# isoCAN.net
KiCad netlist of a schematic drawn in Altium Designer
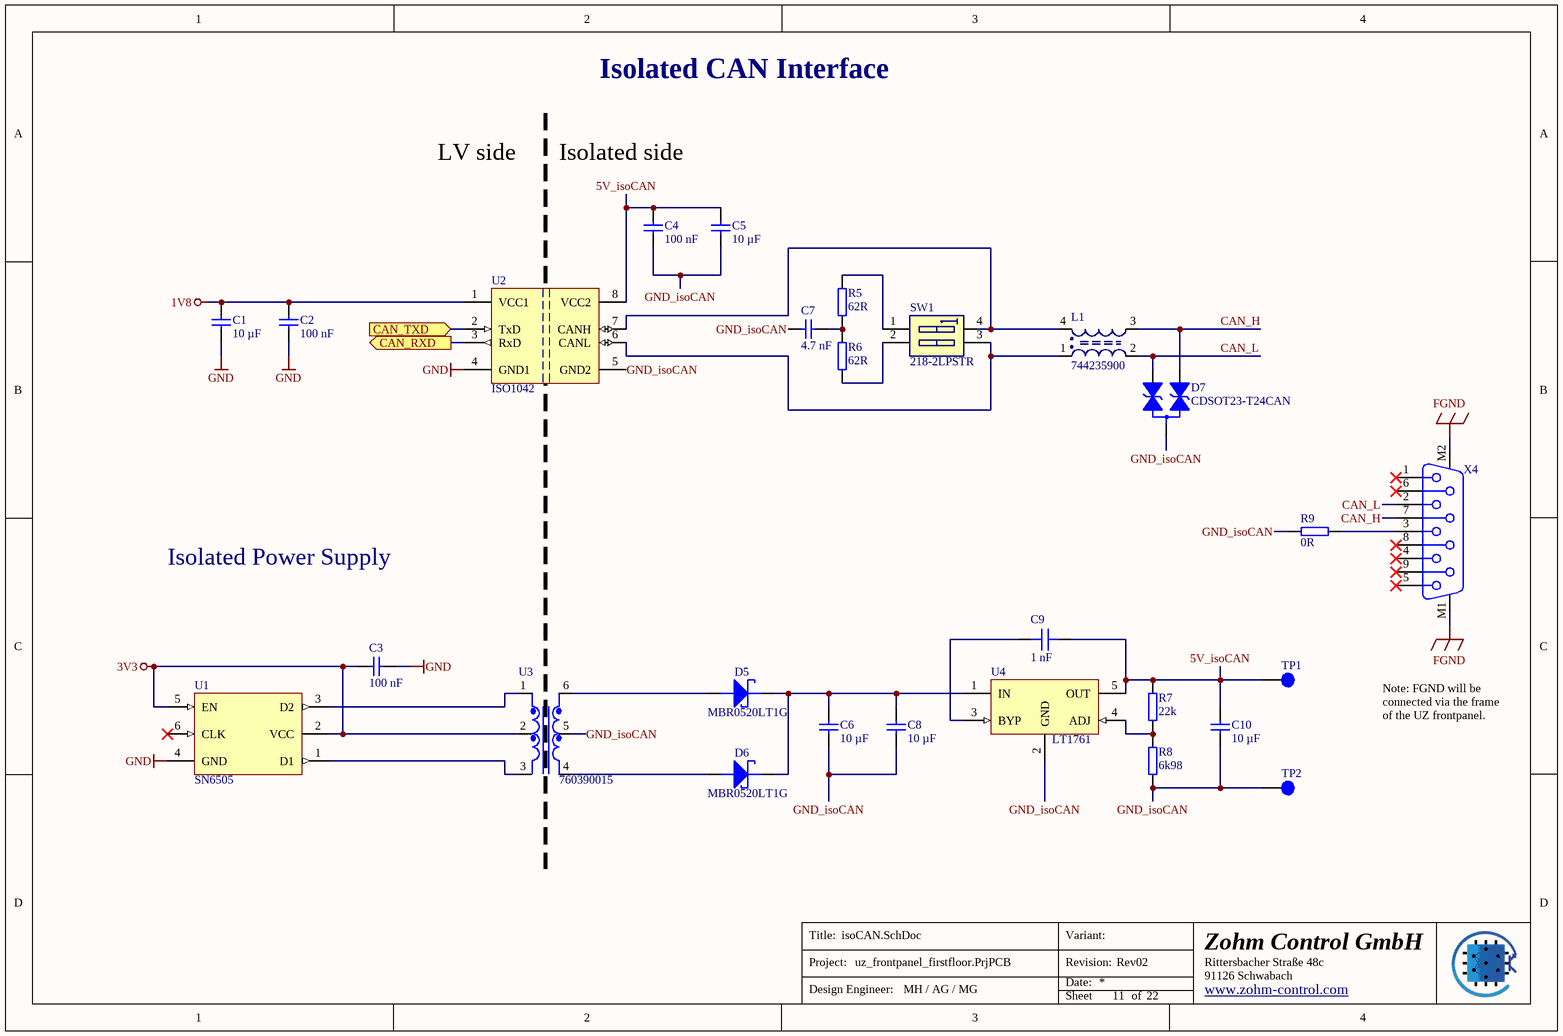
[diagram p0: isoCAN.SchDoc]

(export (version "E")
  (design (tool "Eeschema 10.0.6"))
  (components
    (comp (ref "C1")
      (value "10 µF")
      (footprint "C_0603_TE")
      (description "Generic capacitor")
      (fields
        (field (name "MANUFACTURER PART NUMBER") "UZgen_C_0603_10uF_16V_X7R")
        (field (name "MANUFACTURER") "UZgen")
        (field (name "CREATED FROM") "UZgenTool")
      )
      (libsource (lib "user") (part "CAP-NP"))
    )
    (comp (ref "C2")
      (value "100 nF")
      (footprint "C_0603_TE")
      (description "Generic capacitor")
      (fields
        (field (name "MANUFACTURER PART NUMBER") "UZgen_C_0603_100nF_50V_X7R")
        (field (name "MANUFACTURER") "UZgen")
        (field (name "CREATED FROM") "AGeiger")
      )
      (libsource (lib "user") (part "CAP-NP"))
    )
    (comp (ref "C3")
      (value "100 nF")
      (footprint "C_0603_TE")
      (description "Generic capacitor")
      (fields
        (field (name "MANUFACTURER PART NUMBER") "UZgen_C_0603_100nF_50V_X7R")
        (field (name "MANUFACTURER") "UZgen")
        (field (name "CREATED FROM") "AGeiger")
      )
      (libsource (lib "user") (part "CAP-NP"))
    )
    (comp (ref "C4")
      (value "100 nF")
      (footprint "C_0603_TE")
      (description "Generic capacitor")
      (fields
        (field (name "MANUFACTURER PART NUMBER") "UZgen_C_0603_100nF_50V_X7R")
        (field (name "MANUFACTURER") "UZgen")
        (field (name "CREATED FROM") "AGeiger")
      )
      (libsource (lib "user") (part "CAP-NP"))
    )
    (comp (ref "C5")
      (value "10 µF")
      (footprint "C_0603_TE")
      (description "Generic capacitor")
      (fields
        (field (name "MANUFACTURER PART NUMBER") "UZgen_C_0603_10uF_16V_X7R")
        (field (name "MANUFACTURER") "UZgen")
        (field (name "CREATED FROM") "UZgenTool")
      )
      (libsource (lib "user") (part "CAP-NP"))
    )
    (comp (ref "C6")
      (value "10 µF")
      (footprint "C_0603_TE")
      (description "Generic capacitor")
      (fields
        (field (name "MANUFACTURER PART NUMBER") "UZgen_C_0603_10uF_16V_X7R")
        (field (name "MANUFACTURER") "UZgen")
        (field (name "CREATED FROM") "UZgenTool")
      )
      (libsource (lib "user") (part "CAP-NP"))
    )
    (comp (ref "C7")
      (value "4.7 nF")
      (footprint "C_0603_TE")
      (description "Generic capacitor")
      (fields
        (field (name "MANUFACTURER PART NUMBER") "UZgen_C_0603_4.7nF_50V_X7R")
        (field (name "MANUFACTURER") "UZgen")
        (field (name "CREATED FROM") "UZgenTool")
      )
      (libsource (lib "user") (part "CAP-NP"))
    )
    (comp (ref "C8")
      (value "10 µF")
      (footprint "C_0603_TE")
      (description "Generic capacitor")
      (fields
        (field (name "MANUFACTURER PART NUMBER") "UZgen_C_0603_10uF_16V_X7R")
        (field (name "MANUFACTURER") "UZgen")
        (field (name "CREATED FROM") "UZgenTool")
      )
      (libsource (lib "user") (part "CAP-NP"))
    )
    (comp (ref "C9")
      (value "1 nF")
      (footprint "C_0603")
      (description "Capacitor 0603, 50 VDC, 1 nF, NP0")
      (fields
        (field (name "MANUFACTURER PART NUMBER") "CC0603JRNPO9BN102")
        (field (name "MANUFACTURER") "YAGEO")
        (field (name "CREATED FROM") "AGeiger")
      )
      (libsource (lib "user") (part "Capacitor"))
    )
    (comp (ref "C10")
      (value "10 µF")
      (footprint "C_0603_TE")
      (description "Generic capacitor")
      (fields
        (field (name "MANUFACTURER PART NUMBER") "UZgen_C_0603_10uF_16V_X7R")
        (field (name "MANUFACTURER") "UZgen")
        (field (name "CREATED FROM") "UZgenTool")
      )
      (libsource (lib "user") (part "CAP-NP"))
    )
    (comp (ref "D5")
      (value "MBR0520LT1G")
      (footprint "SOD3816X120N")
      (description "Schottky Diodes & Rectifiers 0.5A 20V")
      (fields
        (field (name "VOLTAGE") "0.5A")
        (field (name "MANUFACTURER") "onsemi")
        (field (name "CREATED FROM") "FRosner")
      )
      (libsource (lib "user") (part "Schottky_Diode"))
    )
    (comp (ref "D6")
      (value "MBR0520LT1G")
      (footprint "SOD3816X120N")
      (description "Schottky Diodes & Rectifiers 0.5A 20V")
      (fields
        (field (name "VOLTAGE") "0.5A")
        (field (name "MANUFACTURER") "onsemi")
        (field (name "CREATED FROM") "FRosner")
      )
      (libsource (lib "user") (part "Schottky_Diode"))
    )
    (comp (ref "D7")
      (value "CDSOT23-T24CAN")
      (footprint "SOT95P237X112-3N")
      (description "ESD Protection Diodes / TVS Diodes SOT-23 24V CANbus")
      (fields
        (field (name "MANUFACTURER") "Bourns")
        (field (name "LCSC PART NUMBER") "C2959841")
        (field (name "CREATED FROM") "AGeiger")
      )
      (libsource (lib "user") (part "SM712"))
    )
    (comp (ref "L1")
      (value "744235900")
      (footprint "WE-CNSW-1812")
      (description "Common Mode Chokes / Filters WE-CNSW 1812 2000mA 0.3uH 100kHz AECQ200")
      (fields (field (name "MANUFACTURER") "Wuerth Elektronik") (field (name "CREATED FROM") "MGremer"))
      (libsource (lib "user") (part "744235900"))
    )
    (comp (ref "R5")
      (value "62R")
      (footprint "R_0603_TE")
      (description "Generic resistor")
      (fields
        (field (name "MANUFACTURER PART NUMBER") "UZgen_R_0603_62R")
        (field (name "MANUFACTURER") "UZgen")
        (field (name "CREATED FROM") "UZgenTool")
      )
      (libsource (lib "user") (part "RES"))
    )
    (comp (ref "R6")
      (value "62R")
      (footprint "R_0603_TE")
      (description "Generic resistor")
      (fields
        (field (name "MANUFACTURER PART NUMBER") "UZgen_R_0603_62R")
        (field (name "MANUFACTURER") "UZgen")
        (field (name "CREATED FROM") "UZgenTool")
      )
      (libsource (lib "user") (part "RES"))
    )
    (comp (ref "R7")
      (value "22k")
      (footprint "R_0603_TE")
      (description "Generic resistor")
      (fields
        (field (name "MANUFACTURER PART NUMBER") "UZgen_R_0603_22k")
        (field (name "MANUFACTURER") "UZgen")
        (field (name "CREATED FROM") "UZgenTool")
      )
      (libsource (lib "user") (part "RES"))
    )
    (comp (ref "R8")
      (value "6k98")
      (footprint "RES 0603_1608")
      (description "SMD resistor 1%")
      (fields
        (field (name "MANUFACTURER PART NUMBER") "RC0603FR-076K98L")
        (field (name "MANUFACTURER") "YAGEO")
        (field (name "CREATED FROM") "AGeiger")
      )
      (libsource (lib "user") (part "Resistor"))
    )
    (comp (ref "R9")
      (value "0R")
      (footprint "R_0603_TE")
      (description "Generic resistor")
      (fields
        (field (name "MANUFACTURER PART NUMBER") "UZgen_R_0603_0R")
        (field (name "MANUFACTURER") "UZgen")
        (field (name "CREATED FROM") "UZgenTool")
      )
      (libsource (lib "user") (part "RES"))
    )
    (comp (ref "SW1")
      (value "218-2LPSTR")
      (footprint "2182LPSTR")
      (description "DIP Switches/SIP Switches SPST 2 switch sections")
      (fields
        (field (name "MANUFACTURER") "CTS Electronic Components")
        (field (name "LCSC PART NUMBER") "C2961921")
        (field (name "CREATED FROM") "AGeiger")
      )
      (libsource (lib "user") (part "218-2LPSTR"))
    )
    (comp (ref "TP1")
      (value "Testpoint 1mm")
      (footprint "TP_1mm")
      (fields
        (field (name "MANUFACTURER PART NUMBER") "NULL")
        (field (name "CREATED") "2018_06_25_AGeiger")
        (field (name "CREATED FROM") "AGeiger")
      )
      (libsource (lib "user") (part "TP_1mm"))
    )
    (comp (ref "TP2")
      (value "Testpoint 1mm")
      (footprint "TP_1mm")
      (fields
        (field (name "MANUFACTURER PART NUMBER") "NULL")
        (field (name "CREATED") "2018_06_25_AGeiger")
        (field (name "CREATED FROM") "AGeiger")
      )
      (libsource (lib "user") (part "TP_1mm"))
    )
    (comp (ref "U1")
      (value "SN6505")
      (footprint "SOT95P280X145-6N")
      (description "Low-Noise 1-A Transformer Drivers for Isolated Power Supplies")
      (fields
        (field (name "MANUFACTURER PART NUMBER") "SN6505BDBVR")
        (field (name "MANUFACTURER") "Texas Instruments")
        (field (name "CREATED FROM") "MGremer/AGeiger/MGeier")
      )
      (libsource (lib "user") (part "SN6505"))
    )
    (comp (ref "U2")
      (value "ISO1042")
      (footprint "SOIC127P1150X280-8L50N")
      (fields
        (field (name "MANUFACTURER") "Texas Instruments")
        (field (name "MANUFACTURER PART NUMBER") "ISO1042BDWVR")
        (field (name "LCSC PART NUMBER") "C484409")
        (field (name "CREATED FROM") "AGeiger")
      )
      (libsource (lib "user") (part "ISO1042xDWVR"))
    )
    (comp (ref "U3")
      (value "760390015")
      (footprint "760390015")
      (description "MID-PPTI Push-Pull Transformers for Texas Instruments; belongs to SN74AVC4T774RSVR")
      (fields
        (field (name "MANUFACTURER") "Wuerth Elektronik")
        (field (name "LCSC PART NUMBER") "C249186")
        (field (name "CREATED FROM") "MGremer")
      )
      (libsource (lib "user") (part "WE-760390015"))
    )
    (comp (ref "U4")
      (value "LT1761")
      (footprint "SOT23-5_N")
      (description "100mA, Low Noise, LDO Micropower Regulators")
      (fields
        (field (name "MANUFACTURER") "Linear Technology")
        (field (name "MANUFACTURER PART NUMBER") "LT1761ES5-BYP#TRPBF")
        (field (name "CREATED FROM") "MGremer")
      )
      (libsource (lib "user") (part "LT1761-BYP"))
    )
    (comp (ref "X4")
      (value "D-SUB 9, female")
      (footprint "618009231121")
      (description "D-Sub Standard Connectors WR-DSUB Female PCB 9Pin Hex Scrw 8.08mm")
      (fields
        (field (name "MANUFACTURER PART NUMBER") "618009231121")
        (field (name "MANUFACTURER") "Wuerth Elektronik")
        (field (name "CREATED FROM") "AGeiger")
      )
      (libsource (lib "user") (part "618009231121"))
    )
  )
  (nets
    (net (code "1") (name "/5V_isoCAN") (class "Default")
      (node (ref "C10") (pin "2") (pinfunction "2_2") (pintype "passive"))
      (node (ref "C4") (pin "2") (pinfunction "2_2") (pintype "passive"))
      (node (ref "C5") (pin "2") (pinfunction "2_2") (pintype "passive"))
      (node (ref "C9") (pin "2") (pinfunction "2_2") (pintype "passive"))
      (node (ref "R7") (pin "2") (pinfunction "2_2") (pintype "passive"))
      (node (ref "TP1") (pin "1") (pintype "passive"))
      (node (ref "U2") (pin "8") (pinfunction "VCC2_8") (pintype "power_in"))
      (node (ref "U4") (pin "5") (pinfunction "OUT_5") (pintype "power_in"))
    )
    (net (code "2") (name "/CAN_H") (class "Default")
      (node (ref "D7") (pin "1") (pinfunction "cathode_1_1") (pintype "passive"))
      (node (ref "L1") (pin "3") (pinfunction "3_3") (pintype "passive"))
      (node (ref "X4") (pin "7") (pinfunction "7_7") (pintype "passive"))
    )
    (net (code "3") (name "/CAN_L") (class "Default")
      (node (ref "D7") (pin "2") (pinfunction "cathode_2_2") (pintype "passive"))
      (node (ref "L1") (pin "2") (pinfunction "2_2") (pintype "passive"))
      (node (ref "X4") (pin "2") (pinfunction "2_2") (pintype "passive"))
    )
    (net (code "4") (name "/CAN_RXD") (class "Default")
      (node (ref "U2") (pin "3") (pinfunction "RxD_3") (pintype "output"))
    )
    (net (code "5") (name "/CAN_TXD") (class "Default")
      (node (ref "U2") (pin "2") (pinfunction "TxD_2") (pintype "input"))
    )
    (net (code "6") (name "/GND_isoCAN") (class "Default")
      (node (ref "C10") (pin "1") (pinfunction "1_1") (pintype "passive"))
      (node (ref "C4") (pin "1") (pinfunction "1_1") (pintype "passive"))
      (node (ref "C5") (pin "1") (pinfunction "1_1") (pintype "passive"))
      (node (ref "C6") (pin "1") (pinfunction "1_1") (pintype "passive"))
      (node (ref "C7") (pin "2") (pinfunction "2_2") (pintype "passive"))
      (node (ref "C8") (pin "1") (pinfunction "1_1") (pintype "passive"))
      (node (ref "D7") (pin "3") (pinfunction "common_cathode_3") (pintype "passive"))
      (node (ref "R8") (pin "1") (pinfunction "1_1") (pintype "passive"))
      (node (ref "R9") (pin "1") (pinfunction "1_1") (pintype "passive"))
      (node (ref "TP2") (pin "1") (pintype "passive"))
      (node (ref "U2") (pin "5") (pinfunction "GND2_5") (pintype "power_in"))
      (node (ref "U3") (pin "5") (pinfunction "5_5") (pintype "passive"))
      (node (ref "U4") (pin "2") (pinfunction "GND_2") (pintype "power_in"))
    )
    (net (code "7") (name "1V8") (class "Default")
      (node (ref "C1") (pin "2") (pinfunction "2_2") (pintype "passive"))
      (node (ref "C2") (pin "2") (pinfunction "2_2") (pintype "passive"))
      (node (ref "U2") (pin "1") (pinfunction "VCC1_1") (pintype "power_in"))
    )
    (net (code "8") (name "3V3") (class "Default")
      (node (ref "C3") (pin "2") (pinfunction "2_2") (pintype "passive"))
      (node (ref "U1") (pin "2") (pinfunction "VCC_2") (pintype "power_in"))
      (node (ref "U1") (pin "5") (pinfunction "EN_5") (pintype "input"))
      (node (ref "U3") (pin "2") (pinfunction "2_2") (pintype "passive"))
    )
    (net (code "9") (name "FGND") (class "Default")
      (node (ref "X4") (pin "M1") (pinfunction "M1_M1") (pintype "passive"))
      (node (ref "X4") (pin "M2") (pinfunction "M2_M2") (pintype "passive"))
    )
    (net (code "10") (name "GND") (class "Default")
      (node (ref "C1") (pin "1") (pinfunction "1_1") (pintype "passive"))
      (node (ref "C2") (pin "1") (pinfunction "1_1") (pintype "passive"))
      (node (ref "C3") (pin "1") (pinfunction "1_1") (pintype "passive"))
      (node (ref "U1") (pin "4") (pinfunction "GND_4") (pintype "power_in"))
      (node (ref "U2") (pin "4") (pinfunction "GND1_4") (pintype "power_in"))
    )
    (net (code "11") (name "Net-(C7-Pad1)") (class "Default")
      (node (ref "C7") (pin "1") (pinfunction "1_1") (pintype "passive"))
      (node (ref "R5") (pin "1") (pinfunction "1_1") (pintype "passive"))
      (node (ref "R6") (pin "2") (pinfunction "2_2") (pintype "passive"))
    )
    (net (code "12") (name "Net-(D5-ANODE)") (class "Default")
      (node (ref "D5") (pin "2") (pinfunction "ANODE_2") (pintype "passive"))
      (node (ref "U3") (pin "6") (pinfunction "6_6") (pintype "passive"))
    )
    (net (code "13") (name "Net-(D5-KATHODE)") (class "Default")
      (node (ref "C6") (pin "2") (pinfunction "2_2") (pintype "passive"))
      (node (ref "C8") (pin "2") (pinfunction "2_2") (pintype "passive"))
      (node (ref "D5") (pin "1") (pinfunction "KATHODE_1") (pintype "passive"))
      (node (ref "D6") (pin "1") (pinfunction "KATHODE_1") (pintype "passive"))
      (node (ref "U4") (pin "1") (pinfunction "IN_1") (pintype "power_in"))
    )
    (net (code "14") (name "Net-(D6-ANODE)") (class "Default")
      (node (ref "D6") (pin "2") (pinfunction "ANODE_2") (pintype "passive"))
      (node (ref "U3") (pin "4") (pinfunction "4_4") (pintype "passive"))
    )
    (net (code "15") (name "Net-(R5-Pad2)") (class "Default")
      (node (ref "R5") (pin "2") (pinfunction "2_2") (pintype "passive"))
      (node (ref "SW1") (pin "1") (pinfunction "1_1") (pintype "passive"))
    )
    (net (code "16") (name "Net-(R6-Pad1)") (class "Default")
      (node (ref "R6") (pin "1") (pinfunction "1_1") (pintype "passive"))
      (node (ref "SW1") (pin "2") (pinfunction "2_2") (pintype "passive"))
    )
    (net (code "17") (name "Net-(R9-Pad2)") (class "Default")
      (node (ref "R9") (pin "2") (pinfunction "2_2") (pintype "passive"))
      (node (ref "X4") (pin "3") (pinfunction "3_3") (pintype "passive"))
    )
    (net (code "18") (name "Net-(U1-D1)") (class "Default")
      (node (ref "U1") (pin "1") (pinfunction "D1_1") (pintype "output"))
      (node (ref "U3") (pin "3") (pinfunction "3_3") (pintype "passive"))
    )
    (net (code "19") (name "Net-(U1-D2)") (class "Default")
      (node (ref "U1") (pin "3") (pinfunction "D2_3") (pintype "output"))
      (node (ref "U3") (pin "1") (pinfunction "1_1") (pintype "passive"))
    )
    (net (code "20") (name "Net-(U2-CANH)") (class "Default")
      (node (ref "L1") (pin "4") (pinfunction "4_4") (pintype "passive"))
      (node (ref "SW1") (pin "4") (pinfunction "4_4") (pintype "passive"))
      (node (ref "U2") (pin "7") (pinfunction "CANH_7") (pintype "bidirectional"))
    )
    (net (code "21") (name "Net-(U2-CANL)") (class "Default")
      (node (ref "L1") (pin "1") (pinfunction "1_1") (pintype "passive"))
      (node (ref "SW1") (pin "3") (pinfunction "3_3") (pintype "passive"))
      (node (ref "U2") (pin "6") (pinfunction "CANL_6") (pintype "bidirectional"))
    )
    (net (code "22") (name "Net-(U4-ADJ)") (class "Default")
      (node (ref "R7") (pin "1") (pinfunction "1_1") (pintype "passive"))
      (node (ref "R8") (pin "2") (pinfunction "2_2") (pintype "passive"))
      (node (ref "U4") (pin "4") (pinfunction "ADJ_4") (pintype "input"))
    )
    (net (code "23") (name "Net-(U4-BYP)") (class "Default")
      (node (ref "C9") (pin "1") (pinfunction "1_1") (pintype "passive"))
      (node (ref "U4") (pin "3") (pinfunction "BYP_3") (pintype "input"))
    )
    (net (code "24") (name "unconnected-(U1-CLK-Pad6)") (class "Default")
      (node (ref "U1") (pin "6") (pinfunction "CLK_6") (pintype "input+no_connect"))
    )
    (net (code "25") (name "unconnected-(X4-Pad1)") (class "Default")
      (node (ref "X4") (pin "1") (pinfunction "1_1") (pintype "passive+no_connect"))
    )
    (net (code "26") (name "unconnected-(X4-Pad4)") (class "Default")
      (node (ref "X4") (pin "4") (pinfunction "4_4") (pintype "passive+no_connect"))
    )
    (net (code "27") (name "unconnected-(X4-Pad5)") (class "Default")
      (node (ref "X4") (pin "5") (pinfunction "5_5") (pintype "passive+no_connect"))
    )
    (net (code "28") (name "unconnected-(X4-Pad6)") (class "Default")
      (node (ref "X4") (pin "6") (pinfunction "6_6") (pintype "passive+no_connect"))
    )
    (net (code "29") (name "unconnected-(X4-Pad8)") (class "Default")
      (node (ref "X4") (pin "8") (pinfunction "8_8") (pintype "passive+no_connect"))
    )
    (net (code "30") (name "unconnected-(X4-Pad9)") (class "Default")
      (node (ref "X4") (pin "9") (pinfunction "9_9") (pintype "passive+no_connect"))
    )
  )
)
